# design.net
KiCad netlist of a schematic drawn in Altium Designer
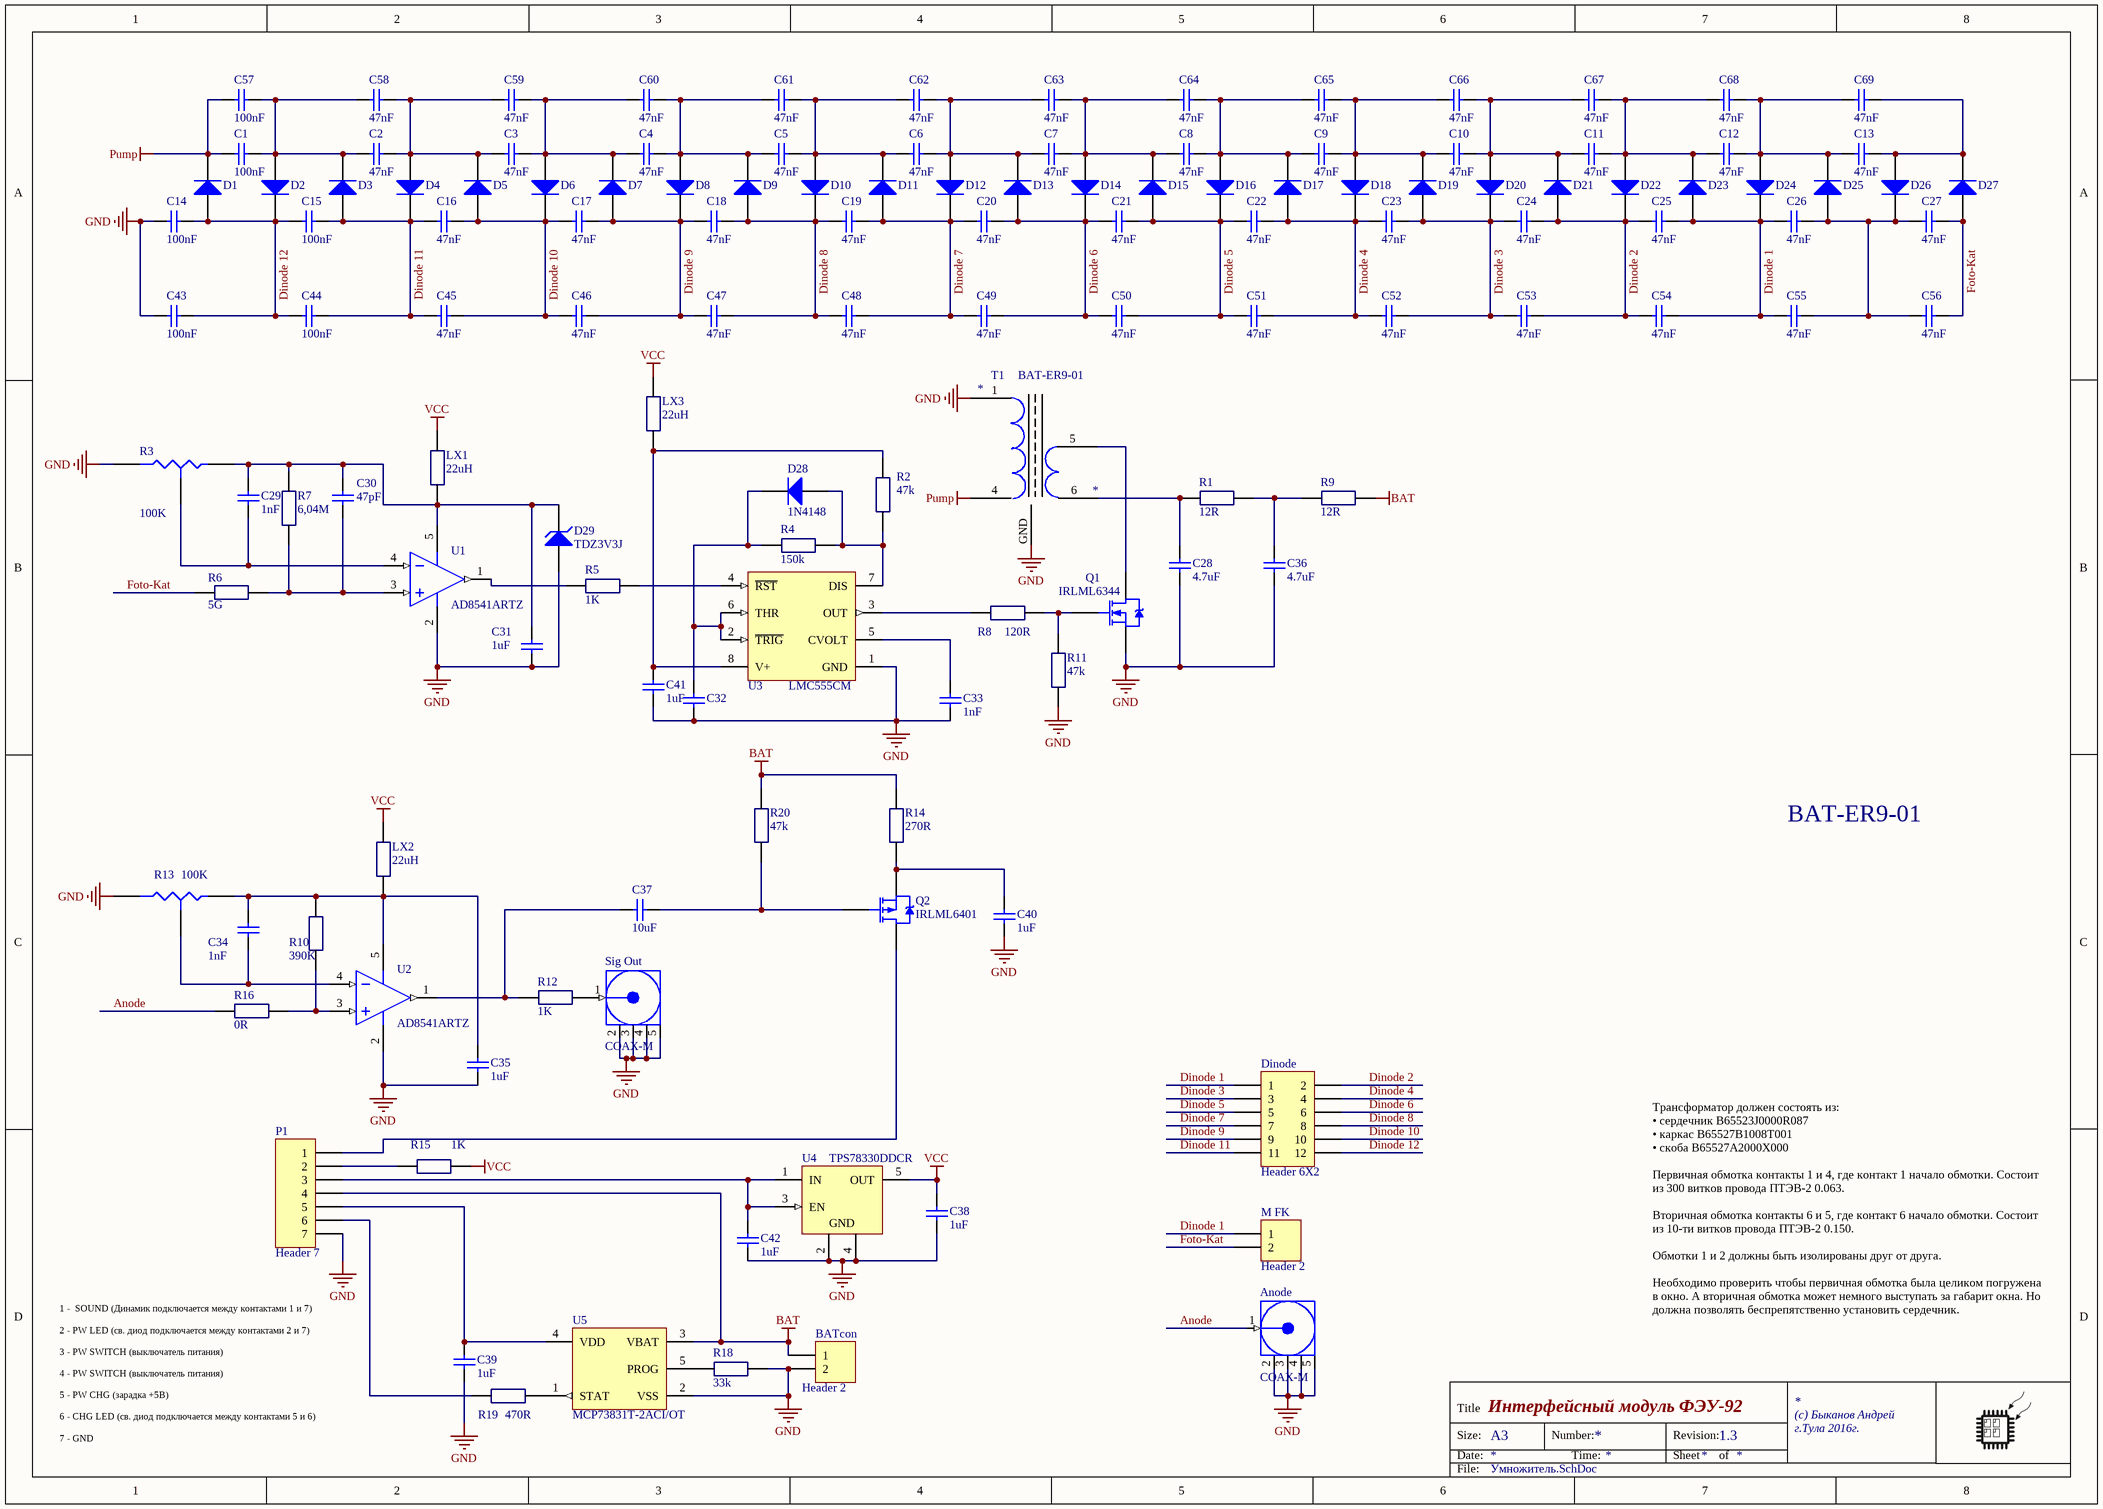
[diagram p0: Умножитель.SchDoc]

(export (version "E")
  (design (tool "Eeschema 10.0.6"))
  (components
    (comp (ref "Anode")
      (value "COAX-M")
      (footprint "MMCX2.54-V5")
      (description "RF Coaxial PCB Connector, MMCX; Thru-Hole, Vertical Mount Plug,  50 Ohm Impedance")
      (libsource (lib "Miscellaneous Connectors") (part "COAX-M"))
    )
    (comp (ref "BATcon")
      (value "Header 2")
      (footprint "LIR2430")
      (description "Header, 2-Pin")
      (libsource (lib "Miscellaneous Connectors") (part "Header 2"))
    )
    (comp (ref "C1")
      (value "100nF")
      (footprint "Miscellaneous Devices:C1206")
      (description "Capacitor (Semiconductor SIM Model)")
      (libsource (lib "Miscellaneous Devices") (part "Cap Semi"))
    )
    (comp (ref "C2")
      (value "47nF")
      (footprint "0805_CAP")
      (description "Capacitor (Semiconductor SIM Model)")
      (libsource (lib "Miscellaneous Devices") (part "Cap Semi"))
    )
    (comp (ref "C3")
      (value "47nF")
      (footprint "0805_CAP")
      (description "Capacitor (Semiconductor SIM Model)")
      (libsource (lib "Miscellaneous Devices") (part "Cap Semi"))
    )
    (comp (ref "C4")
      (value "47nF")
      (footprint "0805_CAP")
      (description "Capacitor (Semiconductor SIM Model)")
      (libsource (lib "Miscellaneous Devices") (part "Cap Semi"))
    )
    (comp (ref "C5")
      (value "47nF")
      (footprint "0805_CAP")
      (description "Capacitor (Semiconductor SIM Model)")
      (libsource (lib "Miscellaneous Devices") (part "Cap Semi"))
    )
    (comp (ref "C6")
      (value "47nF")
      (footprint "0805_CAP")
      (description "Capacitor (Semiconductor SIM Model)")
      (libsource (lib "Miscellaneous Devices") (part "Cap Semi"))
    )
    (comp (ref "C7")
      (value "47nF")
      (footprint "0805_CAP")
      (description "Capacitor (Semiconductor SIM Model)")
      (libsource (lib "Miscellaneous Devices") (part "Cap Semi"))
    )
    (comp (ref "C8")
      (value "47nF")
      (footprint "0805_CAP")
      (description "Capacitor (Semiconductor SIM Model)")
      (libsource (lib "Miscellaneous Devices") (part "Cap Semi"))
    )
    (comp (ref "C9")
      (value "47nF")
      (footprint "0805_CAP")
      (description "Capacitor (Semiconductor SIM Model)")
      (libsource (lib "Miscellaneous Devices") (part "Cap Semi"))
    )
    (comp (ref "C10")
      (value "47nF")
      (footprint "0805_CAP")
      (description "Capacitor (Semiconductor SIM Model)")
      (libsource (lib "Miscellaneous Devices") (part "Cap Semi"))
    )
    (comp (ref "C11")
      (value "47nF")
      (footprint "0805_CAP")
      (description "Capacitor (Semiconductor SIM Model)")
      (libsource (lib "Miscellaneous Devices") (part "Cap Semi"))
    )
    (comp (ref "C12")
      (value "47nF")
      (footprint "0805_CAP")
      (description "Capacitor (Semiconductor SIM Model)")
      (libsource (lib "Miscellaneous Devices") (part "Cap Semi"))
    )
    (comp (ref "C13")
      (value "47nF")
      (footprint "0805_CAP")
      (description "Capacitor (Semiconductor SIM Model)")
      (libsource (lib "Miscellaneous Devices") (part "Cap Semi"))
    )
    (comp (ref "C14")
      (value "100nF")
      (footprint "Miscellaneous Devices:C1206")
      (description "Capacitor (Semiconductor SIM Model)")
      (libsource (lib "Miscellaneous Devices") (part "Cap Semi"))
    )
    (comp (ref "C15")
      (value "100nF")
      (footprint "Miscellaneous Devices:C1206")
      (description "Capacitor (Semiconductor SIM Model)")
      (libsource (lib "Miscellaneous Devices") (part "Cap Semi"))
    )
    (comp (ref "C16")
      (value "47nF")
      (footprint "0805_CAP")
      (description "Capacitor (Semiconductor SIM Model)")
      (libsource (lib "Miscellaneous Devices") (part "Cap Semi"))
    )
    (comp (ref "C17")
      (value "47nF")
      (footprint "0805_CAP")
      (description "Capacitor (Semiconductor SIM Model)")
      (libsource (lib "Miscellaneous Devices") (part "Cap Semi"))
    )
    (comp (ref "C18")
      (value "47nF")
      (footprint "0805_CAP")
      (description "Capacitor (Semiconductor SIM Model)")
      (libsource (lib "Miscellaneous Devices") (part "Cap Semi"))
    )
    (comp (ref "C19")
      (value "47nF")
      (footprint "0805_CAP")
      (description "Capacitor (Semiconductor SIM Model)")
      (libsource (lib "Miscellaneous Devices") (part "Cap Semi"))
    )
    (comp (ref "C20")
      (value "47nF")
      (footprint "0805_CAP")
      (description "Capacitor (Semiconductor SIM Model)")
      (libsource (lib "Miscellaneous Devices") (part "Cap Semi"))
    )
    (comp (ref "C21")
      (value "47nF")
      (footprint "0805_CAP")
      (description "Capacitor (Semiconductor SIM Model)")
      (libsource (lib "Miscellaneous Devices") (part "Cap Semi"))
    )
    (comp (ref "C22")
      (value "47nF")
      (footprint "0805_CAP")
      (description "Capacitor (Semiconductor SIM Model)")
      (libsource (lib "Miscellaneous Devices") (part "Cap Semi"))
    )
    (comp (ref "C23")
      (value "47nF")
      (footprint "0805_CAP")
      (description "Capacitor (Semiconductor SIM Model)")
      (libsource (lib "Miscellaneous Devices") (part "Cap Semi"))
    )
    (comp (ref "C24")
      (value "47nF")
      (footprint "0805_CAP")
      (description "Capacitor (Semiconductor SIM Model)")
      (libsource (lib "Miscellaneous Devices") (part "Cap Semi"))
    )
    (comp (ref "C25")
      (value "47nF")
      (footprint "0805_CAP")
      (description "Capacitor (Semiconductor SIM Model)")
      (libsource (lib "Miscellaneous Devices") (part "Cap Semi"))
    )
    (comp (ref "C26")
      (value "47nF")
      (footprint "0805_CAP")
      (description "Capacitor (Semiconductor SIM Model)")
      (libsource (lib "Miscellaneous Devices") (part "Cap Semi"))
    )
    (comp (ref "C27")
      (value "47nF")
      (footprint "0805_CAP")
      (description "Capacitor (Semiconductor SIM Model)")
      (libsource (lib "Miscellaneous Devices") (part "Cap Semi"))
    )
    (comp (ref "C28")
      (value "4.7uF")
      (footprint "Miscellaneous Devices:C1206")
      (description "Capacitor (Semiconductor SIM Model)")
      (libsource (lib "Miscellaneous Devices") (part "Cap Semi"))
    )
    (comp (ref "C29")
      (value "1nF")
      (footprint "1608[0603]_CAP")
      (description "Capacitor (Semiconductor SIM Model)")
      (libsource (lib "Miscellaneous Devices") (part "Cap Semi"))
    )
    (comp (ref "C30")
      (value "47pF")
      (footprint "1608[0603]_CAP")
      (description "Capacitor (Semiconductor SIM Model)")
      (libsource (lib "Miscellaneous Devices") (part "Cap Semi"))
    )
    (comp (ref "C31")
      (value "1uF")
      (footprint "1608[0603]_CAP")
      (description "Capacitor (Semiconductor SIM Model)")
      (libsource (lib "Miscellaneous Devices") (part "Cap Semi"))
    )
    (comp (ref "C32")
      (value "220pF")
      (footprint "1608[0603]_CAP")
      (description "Capacitor (Semiconductor SIM Model)")
      (libsource (lib "Miscellaneous Devices") (part "Cap Semi"))
    )
    (comp (ref "C33")
      (value "1nF")
      (footprint "1608[0603]_CAP")
      (description "Capacitor (Semiconductor SIM Model)")
      (libsource (lib "Miscellaneous Devices") (part "Cap Semi"))
    )
    (comp (ref "C34")
      (value "1nF")
      (footprint "1608[0603]_CAP")
      (description "Capacitor (Semiconductor SIM Model)")
      (libsource (lib "Miscellaneous Devices") (part "Cap Semi"))
    )
    (comp (ref "C35")
      (value "1uF")
      (footprint "1608[0603]_CAP")
      (description "Capacitor (Semiconductor SIM Model)")
      (libsource (lib "Miscellaneous Devices") (part "Cap Semi"))
    )
    (comp (ref "C36")
      (value "4.7uF")
      (footprint "Miscellaneous Devices:C1206")
      (description "Capacitor (Semiconductor SIM Model)")
      (libsource (lib "Miscellaneous Devices") (part "Cap Semi"))
    )
    (comp (ref "C37")
      (value "10uF")
      (footprint "1608[0603]_CAP")
      (description "Capacitor (Semiconductor SIM Model)")
      (libsource (lib "Miscellaneous Devices") (part "Cap Semi"))
    )
    (comp (ref "C38")
      (value "1uF")
      (footprint "1608[0603]_CAP")
      (description "Capacitor (Semiconductor SIM Model)")
      (libsource (lib "Miscellaneous Devices") (part "Cap Semi"))
    )
    (comp (ref "C39")
      (value "1uF")
      (footprint "1608[0603]_CAP")
      (description "Capacitor (Semiconductor SIM Model)")
      (libsource (lib "Miscellaneous Devices") (part "Cap Semi"))
    )
    (comp (ref "C40")
      (value "1uF")
      (footprint "1608[0603]_CAP")
      (description "Capacitor (Semiconductor SIM Model)")
      (libsource (lib "Miscellaneous Devices") (part "Cap Semi"))
    )
    (comp (ref "C41")
      (value "1uF")
      (footprint "1608[0603]_CAP")
      (description "Capacitor (Semiconductor SIM Model)")
      (libsource (lib "Miscellaneous Devices") (part "Cap Semi"))
    )
    (comp (ref "C42")
      (value "1uF")
      (footprint "1608[0603]_CAP")
      (description "Capacitor (Semiconductor SIM Model)")
      (libsource (lib "Miscellaneous Devices") (part "Cap Semi"))
    )
    (comp (ref "C43")
      (value "100nF")
      (footprint "Miscellaneous Devices:C1206")
      (description "Capacitor (Semiconductor SIM Model)")
      (libsource (lib "Miscellaneous Devices") (part "Cap Semi"))
    )
    (comp (ref "C44")
      (value "100nF")
      (footprint "Miscellaneous Devices:C1206")
      (description "Capacitor (Semiconductor SIM Model)")
      (libsource (lib "Miscellaneous Devices") (part "Cap Semi"))
    )
    (comp (ref "C45")
      (value "47nF")
      (footprint "0805_CAP")
      (description "Capacitor (Semiconductor SIM Model)")
      (libsource (lib "Miscellaneous Devices") (part "Cap Semi"))
    )
    (comp (ref "C46")
      (value "47nF")
      (footprint "0805_CAP")
      (description "Capacitor (Semiconductor SIM Model)")
      (libsource (lib "Miscellaneous Devices") (part "Cap Semi"))
    )
    (comp (ref "C47")
      (value "47nF")
      (footprint "0805_CAP")
      (description "Capacitor (Semiconductor SIM Model)")
      (libsource (lib "Miscellaneous Devices") (part "Cap Semi"))
    )
    (comp (ref "C48")
      (value "47nF")
      (footprint "0805_CAP")
      (description "Capacitor (Semiconductor SIM Model)")
      (libsource (lib "Miscellaneous Devices") (part "Cap Semi"))
    )
    (comp (ref "C49")
      (value "47nF")
      (footprint "0805_CAP")
      (description "Capacitor (Semiconductor SIM Model)")
      (libsource (lib "Miscellaneous Devices") (part "Cap Semi"))
    )
    (comp (ref "C50")
      (value "47nF")
      (footprint "0805_CAP")
      (description "Capacitor (Semiconductor SIM Model)")
      (libsource (lib "Miscellaneous Devices") (part "Cap Semi"))
    )
    (comp (ref "C51")
      (value "47nF")
      (footprint "0805_CAP")
      (description "Capacitor (Semiconductor SIM Model)")
      (libsource (lib "Miscellaneous Devices") (part "Cap Semi"))
    )
    (comp (ref "C52")
      (value "47nF")
      (footprint "0805_CAP")
      (description "Capacitor (Semiconductor SIM Model)")
      (libsource (lib "Miscellaneous Devices") (part "Cap Semi"))
    )
    (comp (ref "C53")
      (value "47nF")
      (footprint "0805_CAP")
      (description "Capacitor (Semiconductor SIM Model)")
      (libsource (lib "Miscellaneous Devices") (part "Cap Semi"))
    )
    (comp (ref "C54")
      (value "47nF")
      (footprint "0805_CAP")
      (description "Capacitor (Semiconductor SIM Model)")
      (libsource (lib "Miscellaneous Devices") (part "Cap Semi"))
    )
    (comp (ref "C55")
      (value "47nF")
      (footprint "0805_CAP")
      (description "Capacitor (Semiconductor SIM Model)")
      (libsource (lib "Miscellaneous Devices") (part "Cap Semi"))
    )
    (comp (ref "C56")
      (value "47nF")
      (footprint "0805_CAP")
      (description "Capacitor (Semiconductor SIM Model)")
      (libsource (lib "Miscellaneous Devices") (part "Cap Semi"))
    )
    (comp (ref "C57")
      (value "100nF")
      (footprint "Miscellaneous Devices:C1206")
      (description "Capacitor (Semiconductor SIM Model)")
      (libsource (lib "Miscellaneous Devices") (part "Cap Semi"))
    )
    (comp (ref "C58")
      (value "47nF")
      (footprint "0805_CAP")
      (description "Capacitor (Semiconductor SIM Model)")
      (libsource (lib "Miscellaneous Devices") (part "Cap Semi"))
    )
    (comp (ref "C59")
      (value "47nF")
      (footprint "0805_CAP")
      (description "Capacitor (Semiconductor SIM Model)")
      (libsource (lib "Miscellaneous Devices") (part "Cap Semi"))
    )
    (comp (ref "C60")
      (value "47nF")
      (footprint "0805_CAP")
      (description "Capacitor (Semiconductor SIM Model)")
      (libsource (lib "Miscellaneous Devices") (part "Cap Semi"))
    )
    (comp (ref "C61")
      (value "47nF")
      (footprint "0805_CAP")
      (description "Capacitor (Semiconductor SIM Model)")
      (libsource (lib "Miscellaneous Devices") (part "Cap Semi"))
    )
    (comp (ref "C62")
      (value "47nF")
      (footprint "0805_CAP")
      (description "Capacitor (Semiconductor SIM Model)")
      (libsource (lib "Miscellaneous Devices") (part "Cap Semi"))
    )
    (comp (ref "C63")
      (value "47nF")
      (footprint "0805_CAP")
      (description "Capacitor (Semiconductor SIM Model)")
      (libsource (lib "Miscellaneous Devices") (part "Cap Semi"))
    )
    (comp (ref "C64")
      (value "47nF")
      (footprint "0805_CAP")
      (description "Capacitor (Semiconductor SIM Model)")
      (libsource (lib "Miscellaneous Devices") (part "Cap Semi"))
    )
    (comp (ref "C65")
      (value "47nF")
      (footprint "0805_CAP")
      (description "Capacitor (Semiconductor SIM Model)")
      (libsource (lib "Miscellaneous Devices") (part "Cap Semi"))
    )
    (comp (ref "C66")
      (value "47nF")
      (footprint "0805_CAP")
      (description "Capacitor (Semiconductor SIM Model)")
      (libsource (lib "Miscellaneous Devices") (part "Cap Semi"))
    )
    (comp (ref "C67")
      (value "47nF")
      (footprint "0805_CAP")
      (description "Capacitor (Semiconductor SIM Model)")
      (libsource (lib "Miscellaneous Devices") (part "Cap Semi"))
    )
    (comp (ref "C68")
      (value "47nF")
      (footprint "0805_CAP")
      (description "Capacitor (Semiconductor SIM Model)")
      (libsource (lib "Miscellaneous Devices") (part "Cap Semi"))
    )
    (comp (ref "C69")
      (value "47nF")
      (footprint "0805_CAP")
      (description "Capacitor (Semiconductor SIM Model)")
      (libsource (lib "Miscellaneous Devices") (part "Cap Semi"))
    )
    (comp (ref "D1")
      (value "~")
      (footprint "DA2JF8100L")
      (description "Default Diode")
      (libsource (lib "Miscellaneous Devices") (part "Diode"))
    )
    (comp (ref "D2")
      (value "~")
      (footprint "DA2JF8100L")
      (description "Default Diode")
      (libsource (lib "Miscellaneous Devices") (part "Diode"))
    )
    (comp (ref "D3")
      (value "~")
      (footprint "DA2JF8100L")
      (description "Default Diode")
      (libsource (lib "Miscellaneous Devices") (part "Diode"))
    )
    (comp (ref "D4")
      (value "~")
      (footprint "DA2JF8100L")
      (description "Default Diode")
      (libsource (lib "Miscellaneous Devices") (part "Diode"))
    )
    (comp (ref "D5")
      (value "~")
      (footprint "DA2JF8100L")
      (description "Default Diode")
      (libsource (lib "Miscellaneous Devices") (part "Diode"))
    )
    (comp (ref "D6")
      (value "~")
      (footprint "DA2JF8100L")
      (description "Default Diode")
      (libsource (lib "Miscellaneous Devices") (part "Diode"))
    )
    (comp (ref "D7")
      (value "~")
      (footprint "DA2JF8100L")
      (description "Default Diode")
      (libsource (lib "Miscellaneous Devices") (part "Diode"))
    )
    (comp (ref "D8")
      (value "~")
      (footprint "DA2JF8100L")
      (description "Default Diode")
      (libsource (lib "Miscellaneous Devices") (part "Diode"))
    )
    (comp (ref "D9")
      (value "~")
      (footprint "DA2JF8100L")
      (description "Default Diode")
      (libsource (lib "Miscellaneous Devices") (part "Diode"))
    )
    (comp (ref "D10")
      (value "~")
      (footprint "DA2JF8100L")
      (description "Default Diode")
      (libsource (lib "Miscellaneous Devices") (part "Diode"))
    )
    (comp (ref "D11")
      (value "~")
      (footprint "DA2JF8100L")
      (description "Default Diode")
      (libsource (lib "Miscellaneous Devices") (part "Diode"))
    )
    (comp (ref "D12")
      (value "~")
      (footprint "DA2JF8100L")
      (description "Default Diode")
      (libsource (lib "Miscellaneous Devices") (part "Diode"))
    )
    (comp (ref "D13")
      (value "~")
      (footprint "DA2JF8100L")
      (description "Default Diode")
      (libsource (lib "Miscellaneous Devices") (part "Diode"))
    )
    (comp (ref "D14")
      (value "~")
      (footprint "DA2JF8100L")
      (description "Default Diode")
      (libsource (lib "Miscellaneous Devices") (part "Diode"))
    )
    (comp (ref "D15")
      (value "~")
      (footprint "DA2JF8100L")
      (description "Default Diode")
      (libsource (lib "Miscellaneous Devices") (part "Diode"))
    )
    (comp (ref "D16")
      (value "~")
      (footprint "DA2JF8100L")
      (description "Default Diode")
      (libsource (lib "Miscellaneous Devices") (part "Diode"))
    )
    (comp (ref "D17")
      (value "~")
      (footprint "DA2JF8100L")
      (description "Default Diode")
      (libsource (lib "Miscellaneous Devices") (part "Diode"))
    )
    (comp (ref "D18")
      (value "~")
      (footprint "DA2JF8100L")
      (description "Default Diode")
      (libsource (lib "Miscellaneous Devices") (part "Diode"))
    )
    (comp (ref "D19")
      (value "~")
      (footprint "DA2JF8100L")
      (description "Default Diode")
      (libsource (lib "Miscellaneous Devices") (part "Diode"))
    )
    (comp (ref "D20")
      (value "~")
      (footprint "DA2JF8100L")
      (description "Default Diode")
      (libsource (lib "Miscellaneous Devices") (part "Diode"))
    )
    (comp (ref "D21")
      (value "~")
      (footprint "DA2JF8100L")
      (description "Default Diode")
      (libsource (lib "Miscellaneous Devices") (part "Diode"))
    )
    (comp (ref "D22")
      (value "~")
      (footprint "DA2JF8100L")
      (description "Default Diode")
      (libsource (lib "Miscellaneous Devices") (part "Diode"))
    )
    (comp (ref "D23")
      (value "~")
      (footprint "DA2JF8100L")
      (description "Default Diode")
      (libsource (lib "Miscellaneous Devices") (part "Diode"))
    )
    (comp (ref "D24")
      (value "~")
      (footprint "DA2JF8100L")
      (description "Default Diode")
      (libsource (lib "Miscellaneous Devices") (part "Diode"))
    )
    (comp (ref "D25")
      (value "~")
      (footprint "DA2JF8100L")
      (description "Default Diode")
      (libsource (lib "Miscellaneous Devices") (part "Diode"))
    )
    (comp (ref "D26")
      (value "~")
      (footprint "DA2JF8100L")
      (description "Default Diode")
      (libsource (lib "Miscellaneous Devices") (part "Diode"))
    )
    (comp (ref "D27")
      (value "~")
      (footprint "DA2JF8100L")
      (description "Default Diode")
      (libsource (lib "Miscellaneous Devices") (part "Diode"))
    )
    (comp (ref "D28")
      (value "1N4148")
      (footprint "GRZZ0002ZB-A")
      (description "Silicon Epitaxial Planar Diode for Various Detector, Modulator, Demodulator")
      (libsource (lib "Renesas Diode") (part "1N4148"))
    )
    (comp (ref "D29")
      (value "TDZ3V3J")
      (footprint "SC-90")
      (description "Zener Diode")
      (libsource (lib "Miscellaneous Devices") (part "D Zener"))
    )
    (comp (ref "Dinode")
      (value "Header 6X2")
      (footprint "HDR2X6")
      (description "Header, 6-Pin, Dual row")
      (libsource (lib "Miscellaneous Connectors") (part "Header 6X2"))
    )
    (comp (ref "LX1")
      (value "22uH")
      (footprint "Resistor")
      (libsource (lib "Микрон-3") (part "Resistor 0805"))
    )
    (comp (ref "LX2")
      (value "22uH")
      (footprint "Resistor")
      (libsource (lib "Микрон-3") (part "Resistor 0805"))
    )
    (comp (ref "LX3")
      (value "22uH")
      (footprint "Resistor")
      (libsource (lib "Микрон-3") (part "Resistor 0805"))
    )
    (comp (ref "M FK")
      (value "Header 2")
      (footprint "HDR1X2")
      (description "Header, 2-Pin")
      (libsource (lib "Miscellaneous Connectors") (part "Header 2"))
    )
    (comp (ref "P1")
      (value "Header 7")
      (footprint "HDR1X7")
      (description "Header, 7-Pin")
      (libsource (lib "Miscellaneous Connectors") (part "Header 7"))
    )
    (comp (ref "Q1")
      (value "IRLML6344")
      (footprint "SOT-23_N")
      (description "HEXFET Power MOSFET")
      (libsource (lib "IR Discrete MOSFET - Power") (part "IRLML2402"))
    )
    (comp (ref "Q2")
      (value "IRLML6401")
      (footprint "Micro3_N")
      (description "HEXFET Power MOSFET")
      (libsource (lib "IR Discrete MOSFET - Power") (part "IRLML6401"))
    )
    (comp (ref "R1")
      (value "12R")
      (footprint "1608[0603]_RES")
      (libsource (lib "Микрон-3") (part "Resistor 0805"))
    )
    (comp (ref "R2")
      (value "47k")
      (footprint "1608[0603]_RES")
      (libsource (lib "Микрон-3") (part "Resistor 0805"))
    )
    (comp (ref "R3")
      (value "100K")
      (footprint "3223W")
      (description "Tapped Resistor")
      (libsource (lib "Miscellaneous Devices") (part "Res Tap"))
    )
    (comp (ref "R4")
      (value "150k")
      (footprint "1608[0603]_RES")
      (libsource (lib "Микрон-3") (part "Resistor 0805"))
    )
    (comp (ref "R5")
      (value "1K")
      (footprint "1608[0603]")
      (libsource (lib "Микрон-3") (part "Resistor 0805"))
    )
    (comp (ref "R6")
      (value "5G")
      (footprint "HVF2512T5007FE")
      (libsource (lib "Микрон-3") (part "Resistor 0805"))
    )
    (comp (ref "R7")
      (value "6,04M")
      (footprint "1608[0603]")
      (libsource (lib "Микрон-3") (part "Resistor 0805"))
    )
    (comp (ref "R8")
      (value "120R")
      (footprint "1608[0603]_RES")
      (libsource (lib "Микрон-3") (part "Resistor 0805"))
    )
    (comp (ref "R9")
      (value "12R")
      (footprint "1608[0603]_RES")
      (libsource (lib "Микрон-3") (part "Resistor 0805"))
    )
    (comp (ref "R10")
      (value "390K")
      (footprint "1608[0603]")
      (libsource (lib "Микрон-3") (part "Resistor 0805"))
    )
    (comp (ref "R11")
      (value "47k")
      (footprint "1608[0603]_RES")
      (libsource (lib "Микрон-3") (part "Resistor 0805"))
    )
    (comp (ref "R12")
      (value "1K")
      (footprint "1608[0603]")
      (libsource (lib "Микрон-3") (part "Resistor 0805"))
    )
    (comp (ref "R13")
      (value "100K")
      (footprint "3223W")
      (description "Tapped Resistor")
      (libsource (lib "Miscellaneous Devices") (part "Res Tap"))
    )
    (comp (ref "R14")
      (value "270R")
      (footprint "1608[0603]_RES")
      (libsource (lib "Микрон-3") (part "Resistor 0805"))
    )
    (comp (ref "R15")
      (value "1K")
      (footprint "1608[0603]_RES")
      (libsource (lib "Микрон-3") (part "Resistor 0805"))
    )
    (comp (ref "R16")
      (value "0R")
      (footprint "1608[0603]")
      (libsource (lib "Микрон-3") (part "Resistor 0805"))
    )
    (comp (ref "R18")
      (value "33k")
      (footprint "1608[0603]_RES")
      (libsource (lib "Микрон-3") (part "Resistor 0805"))
    )
    (comp (ref "R19")
      (value "470R")
      (footprint "1608[0603]_RES")
      (libsource (lib "Микрон-3") (part "Resistor 0805"))
    )
    (comp (ref "R20")
      (value "47k")
      (footprint "1608[0603]_RES")
      (libsource (lib "Микрон-3") (part "Resistor 0805"))
    )
    (comp (ref "Sig Out")
      (value "COAX-M")
      (footprint "MMCX2.54-V5")
      (description "RF Coaxial PCB Connector, MMCX; Thru-Hole, Vertical Mount Plug,  50 Ohm Impedance")
      (libsource (lib "Miscellaneous Connectors") (part "COAX-M"))
    )
    (comp (ref "T1")
      (value "BAT-ER9-01")
      (footprint "Epcos ER9.5/5")
      (libsource (lib "My SCH library") (part "Epcos ER9.5/5"))
    )
    (comp (ref "U1")
      (value "AD8541ARTZ")
      (footprint "ADI-RJ-5_N")
      (fields
        (field (name "GENERIC PART NUMBER") "AD8541")
        (field (name "MANUFACTURER") "Analog Devices")
        (field (name "PARTNUMBER") "AD8541ARTZ-R2")
      )
      (libsource (lib "Analog Devices Operational Amplifiers") (part "AD8541ARTZ-R2"))
    )
    (comp (ref "U2")
      (value "AD8541ARTZ")
      (footprint "ADI-RJ-5_N")
      (fields
        (field (name "GENERIC PART NUMBER") "AD8541")
        (field (name "MANUFACTURER") "Analog Devices")
        (field (name "PARTNUMBER") "AD8541ARTZ-R2")
      )
      (libsource (lib "Analog Devices Operational Amplifiers") (part "AD8541ARTZ-R2"))
    )
    (comp (ref "U3")
      (value "LMC555CM")
      (footprint "M08A_N")
      (description "CMOS Timer, 8-pin Narrow SOIC")
      (fields (field (name "MANUFACTURER") "National Semiconductor"))
      (libsource (lib "NSC Analog") (part "LMC555CM"))
    )
    (comp (ref "U4")
      (value "TPS78330DDCR")
      (footprint "TI-DDC5_N")
      (fields (field (name "MANUFACTURER") "Texas Instruments"))
      (libsource (lib "TI Power Management Linear Regulator Single Channel LDO (0-350mA)") (part "TPS78330DDCR"))
    )
    (comp (ref "U5")
      (value "MCP73831T-2ACI/OT")
      (footprint "SOT-23-OT5_N")
      (libsource (lib "Microchip Power Mgt Battery Management") (part "MCP73831T-2ACI/OT"))
    )
  )
  (nets
    (net (code "1") (name "/Anode") (class "Default")
      (node (ref "Anode") (pin "1") (pinfunction "Signal_1") (pintype "input"))
      (node (ref "R16") (pin "1") (pinfunction "A_1") (pintype "passive"))
    )
    (net (code "2") (name "/Dinode 1") (class "Default")
      (node (ref "C25") (pin "1") (pinfunction "1_1") (pintype "passive"))
      (node (ref "C26") (pin "2") (pinfunction "2_2") (pintype "passive"))
      (node (ref "C54") (pin "1") (pinfunction "1_1") (pintype "passive"))
      (node (ref "C55") (pin "2") (pinfunction "2_2") (pintype "passive"))
      (node (ref "D23") (pin "1") (pinfunction "A_1") (pintype "passive"))
      (node (ref "D24") (pin "2") (pinfunction "K_2") (pintype "passive"))
      (node (ref "Dinode") (pin "1") (pinfunction "1_1") (pintype "passive"))
      (node (ref "M FK") (pin "1") (pinfunction "1_1") (pintype "passive"))
    )
    (net (code "3") (name "/Dinode 2") (class "Default")
      (node (ref "C24") (pin "1") (pinfunction "1_1") (pintype "passive"))
      (node (ref "C25") (pin "2") (pinfunction "2_2") (pintype "passive"))
      (node (ref "C53") (pin "1") (pinfunction "1_1") (pintype "passive"))
      (node (ref "C54") (pin "2") (pinfunction "2_2") (pintype "passive"))
      (node (ref "D21") (pin "1") (pinfunction "A_1") (pintype "passive"))
      (node (ref "D22") (pin "2") (pinfunction "K_2") (pintype "passive"))
      (node (ref "Dinode") (pin "2") (pinfunction "2_2") (pintype "passive"))
    )
    (net (code "4") (name "/Dinode 3") (class "Default")
      (node (ref "C23") (pin "1") (pinfunction "1_1") (pintype "passive"))
      (node (ref "C24") (pin "2") (pinfunction "2_2") (pintype "passive"))
      (node (ref "C52") (pin "1") (pinfunction "1_1") (pintype "passive"))
      (node (ref "C53") (pin "2") (pinfunction "2_2") (pintype "passive"))
      (node (ref "D19") (pin "1") (pinfunction "A_1") (pintype "passive"))
      (node (ref "D20") (pin "2") (pinfunction "K_2") (pintype "passive"))
      (node (ref "Dinode") (pin "3") (pinfunction "3_3") (pintype "passive"))
    )
    (net (code "5") (name "/Dinode 4") (class "Default")
      (node (ref "C22") (pin "1") (pinfunction "1_1") (pintype "passive"))
      (node (ref "C23") (pin "2") (pinfunction "2_2") (pintype "passive"))
      (node (ref "C51") (pin "1") (pinfunction "1_1") (pintype "passive"))
      (node (ref "C52") (pin "2") (pinfunction "2_2") (pintype "passive"))
      (node (ref "D17") (pin "1") (pinfunction "A_1") (pintype "passive"))
      (node (ref "D18") (pin "2") (pinfunction "K_2") (pintype "passive"))
      (node (ref "Dinode") (pin "4") (pinfunction "4_4") (pintype "passive"))
    )
    (net (code "6") (name "/Dinode 5") (class "Default")
      (node (ref "C21") (pin "1") (pinfunction "1_1") (pintype "passive"))
      (node (ref "C22") (pin "2") (pinfunction "2_2") (pintype "passive"))
      (node (ref "C50") (pin "1") (pinfunction "1_1") (pintype "passive"))
      (node (ref "C51") (pin "2") (pinfunction "2_2") (pintype "passive"))
      (node (ref "D15") (pin "1") (pinfunction "A_1") (pintype "passive"))
      (node (ref "D16") (pin "2") (pinfunction "K_2") (pintype "passive"))
      (node (ref "Dinode") (pin "5") (pinfunction "5_5") (pintype "passive"))
    )
    (net (code "7") (name "/Dinode 6") (class "Default")
      (node (ref "C20") (pin "1") (pinfunction "1_1") (pintype "passive"))
      (node (ref "C21") (pin "2") (pinfunction "2_2") (pintype "passive"))
      (node (ref "C49") (pin "1") (pinfunction "1_1") (pintype "passive"))
      (node (ref "C50") (pin "2") (pinfunction "2_2") (pintype "passive"))
      (node (ref "D13") (pin "1") (pinfunction "A_1") (pintype "passive"))
      (node (ref "D14") (pin "2") (pinfunction "K_2") (pintype "passive"))
      (node (ref "Dinode") (pin "6") (pinfunction "6_6") (pintype "passive"))
    )
    (net (code "8") (name "/Dinode 7") (class "Default")
      (node (ref "C19") (pin "1") (pinfunction "1_1") (pintype "passive"))
      (node (ref "C20") (pin "2") (pinfunction "2_2") (pintype "passive"))
      (node (ref "C48") (pin "1") (pinfunction "1_1") (pintype "passive"))
      (node (ref "C49") (pin "2") (pinfunction "2_2") (pintype "passive"))
      (node (ref "D11") (pin "1") (pinfunction "A_1") (pintype "passive"))
      (node (ref "D12") (pin "2") (pinfunction "K_2") (pintype "passive"))
      (node (ref "Dinode") (pin "7") (pinfunction "7_7") (pintype "passive"))
    )
    (net (code "9") (name "/Dinode 8") (class "Default")
      (node (ref "C18") (pin "1") (pinfunction "1_1") (pintype "passive"))
      (node (ref "C19") (pin "2") (pinfunction "2_2") (pintype "passive"))
      (node (ref "C47") (pin "1") (pinfunction "1_1") (pintype "passive"))
      (node (ref "C48") (pin "2") (pinfunction "2_2") (pintype "passive"))
      (node (ref "D10") (pin "2") (pinfunction "K_2") (pintype "passive"))
      (node (ref "D9") (pin "1") (pinfunction "A_1") (pintype "passive"))
      (node (ref "Dinode") (pin "8") (pinfunction "8_8") (pintype "passive"))
    )
    (net (code "10") (name "/Dinode 9") (class "Default")
      (node (ref "C17") (pin "1") (pinfunction "1_1") (pintype "passive"))
      (node (ref "C18") (pin "2") (pinfunction "2_2") (pintype "passive"))
      (node (ref "C46") (pin "1") (pinfunction "1_1") (pintype "passive"))
      (node (ref "C47") (pin "2") (pinfunction "2_2") (pintype "passive"))
      (node (ref "D7") (pin "1") (pinfunction "A_1") (pintype "passive"))
      (node (ref "D8") (pin "2") (pinfunction "K_2") (pintype "passive"))
      (node (ref "Dinode") (pin "9") (pinfunction "9_9") (pintype "passive"))
    )
    (net (code "11") (name "/Dinode 10") (class "Default")
      (node (ref "C16") (pin "1") (pinfunction "1_1") (pintype "passive"))
      (node (ref "C17") (pin "2") (pinfunction "2_2") (pintype "passive"))
      (node (ref "C45") (pin "1") (pinfunction "1_1") (pintype "passive"))
      (node (ref "C46") (pin "2") (pinfunction "2_2") (pintype "passive"))
      (node (ref "D5") (pin "1") (pinfunction "A_1") (pintype "passive"))
      (node (ref "D6") (pin "2") (pinfunction "K_2") (pintype "passive"))
      (node (ref "Dinode") (pin "10") (pinfunction "10_10") (pintype "passive"))
    )
    (net (code "12") (name "/Dinode 11") (class "Default")
      (node (ref "C15") (pin "1") (pinfunction "1_1") (pintype "passive"))
      (node (ref "C16") (pin "2") (pinfunction "2_2") (pintype "passive"))
      (node (ref "C44") (pin "1") (pinfunction "1_1") (pintype "passive"))
      (node (ref "C45") (pin "2") (pinfunction "2_2") (pintype "passive"))
      (node (ref "D3") (pin "1") (pinfunction "A_1") (pintype "passive"))
      (node (ref "D4") (pin "2") (pinfunction "K_2") (pintype "passive"))
      (node (ref "Dinode") (pin "11") (pinfunction "11_11") (pintype "passive"))
    )
    (net (code "13") (name "/Dinode 12") (class "Default")
      (node (ref "C14") (pin "1") (pinfunction "1_1") (pintype "passive"))
      (node (ref "C15") (pin "2") (pinfunction "2_2") (pintype "passive"))
      (node (ref "C43") (pin "1") (pinfunction "1_1") (pintype "passive"))
      (node (ref "C44") (pin "2") (pinfunction "2_2") (pintype "passive"))
      (node (ref "D1") (pin "1") (pinfunction "A_1") (pintype "passive"))
      (node (ref "D2") (pin "2") (pinfunction "K_2") (pintype "passive"))
      (node (ref "Dinode") (pin "12") (pinfunction "12_12") (pintype "passive"))
    )
    (net (code "14") (name "/Foto-Kat") (class "Default")
      (node (ref "C27") (pin "1") (pinfunction "1_1") (pintype "passive"))
      (node (ref "C56") (pin "1") (pinfunction "1_1") (pintype "passive"))
      (node (ref "D27") (pin "1") (pinfunction "A_1") (pintype "passive"))
      (node (ref "M FK") (pin "2") (pinfunction "2_2") (pintype "passive"))
      (node (ref "R6") (pin "1") (pinfunction "A_1") (pintype "passive"))
    )
    (net (code "15") (name "BAT") (class "Default")
      (node (ref "BATcon") (pin "1") (pinfunction "1_1") (pintype "passive"))
      (node (ref "P1") (pin "4") (pinfunction "4_4") (pintype "passive"))
      (node (ref "R14") (pin "2") (pinfunction "2_2") (pintype "passive"))
      (node (ref "R20") (pin "1") (pinfunction "A_1") (pintype "passive"))
      (node (ref "R9") (pin "2") (pinfunction "2_2") (pintype "passive"))
      (node (ref "U5") (pin "3") (pinfunction "VBAT_3") (pintype "power_in"))
    )
    (net (code "16") (name "GND") (class "Default")
      (node (ref "Anode") (pin "2") (pinfunction "GND_2") (pintype "power_in"))
      (node (ref "Anode") (pin "3") (pinfunction "GND_3") (pintype "power_in"))
      (node (ref "Anode") (pin "4") (pinfunction "GND_4") (pintype "power_in"))
      (node (ref "Anode") (pin "5") (pinfunction "GND_5") (pintype "power_in"))
      (node (ref "BATcon") (pin "2") (pinfunction "2_2") (pintype "passive"))
      (node (ref "C14") (pin "2") (pinfunction "2_2") (pintype "passive"))
      (node (ref "C28") (pin "2") (pinfunction "2_2") (pintype "passive"))
      (node (ref "C31") (pin "2") (pinfunction "2_2") (pintype "passive"))
      (node (ref "C32") (pin "1") (pinfunction "1_1") (pintype "passive"))
      (node (ref "C33") (pin "2") (pinfunction "2_2") (pintype "passive"))
      (node (ref "C35") (pin "2") (pinfunction "2_2") (pintype "passive"))
      (node (ref "C36") (pin "2") (pinfunction "2_2") (pintype "passive"))
      (node (ref "C38") (pin "1") (pinfunction "1_1") (pintype "passive"))
      (node (ref "C39") (pin "2") (pinfunction "2_2") (pintype "passive"))
      (node (ref "C40") (pin "2") (pinfunction "2_2") (pintype "passive"))
      (node (ref "C41") (pin "2") (pinfunction "2_2") (pintype "passive"))
      (node (ref "C42") (pin "2") (pinfunction "2_2") (pintype "passive"))
      (node (ref "C43") (pin "2") (pinfunction "2_2") (pintype "passive"))
      (node (ref "D29") (pin "1") (pinfunction "A_1") (pintype "passive"))
      (node (ref "P1") (pin "7") (pinfunction "7_7") (pintype "passive"))
      (node (ref "Q1") (pin "2") (pinfunction "S_2") (pintype "passive"))
      (node (ref "R11") (pin "1") (pinfunction "A_1") (pintype "passive"))
      (node (ref "R13") (pin "2") (pinfunction "B_2") (pintype "passive"))
      (node (ref "R18") (pin "2") (pinfunction "2_2") (pintype "passive"))
      (node (ref "R3") (pin "2") (pinfunction "B_2") (pintype "passive"))
      (node (ref "Sig Out") (pin "2") (pinfunction "GND_2") (pintype "power_in"))
      (node (ref "Sig Out") (pin "3") (pinfunction "GND_3") (pintype "power_in"))
      (node (ref "Sig Out") (pin "4") (pinfunction "GND_4") (pintype "power_in"))
      (node (ref "Sig Out") (pin "5") (pinfunction "GND_5") (pintype "power_in"))
      (node (ref "T1") (pin "1") (pinfunction "1_1") (pintype "passive"))
      (node (ref "T1") (pin "GND") (pinfunction "GND_GND") (pintype "passive"))
      (node (ref "U1") (pin "2") (pinfunction "-V_2") (pintype "power_in"))
      (node (ref "U2") (pin "2") (pinfunction "-V_2") (pintype "power_in"))
      (node (ref "U3") (pin "1") (pinfunction "GND_1") (pintype "power_in"))
      (node (ref "U4") (pin "2") (pinfunction "GND_2") (pintype "power_in"))
      (node (ref "U4") (pin "4") (pinfunction "GND_4") (pintype "power_in"))
      (node (ref "U5") (pin "2") (pinfunction "VSS_2") (pintype "power_in"))
    )
    (net (code "17") (name "Net-(D2-A)") (class "Default")
      (node (ref "C1") (pin "1") (pinfunction "1_1") (pintype "passive"))
      (node (ref "C2") (pin "2") (pinfunction "2_2") (pintype "passive"))
      (node (ref "C57") (pin "1") (pinfunction "1_1") (pintype "passive"))
      (node (ref "C58") (pin "2") (pinfunction "2_2") (pintype "passive"))
      (node (ref "D2") (pin "1") (pinfunction "A_1") (pintype "passive"))
      (node (ref "D3") (pin "2") (pinfunction "K_2") (pintype "passive"))
    )
    (net (code "18") (name "Net-(D4-A)") (class "Default")
      (node (ref "C2") (pin "1") (pinfunction "1_1") (pintype "passive"))
      (node (ref "C3") (pin "2") (pinfunction "2_2") (pintype "passive"))
      (node (ref "C58") (pin "1") (pinfunction "1_1") (pintype "passive"))
      (node (ref "C59") (pin "2") (pinfunction "2_2") (pintype "passive"))
      (node (ref "D4") (pin "1") (pinfunction "A_1") (pintype "passive"))
      (node (ref "D5") (pin "2") (pinfunction "K_2") (pintype "passive"))
    )
    (net (code "19") (name "Net-(D6-A)") (class "Default")
      (node (ref "C3") (pin "1") (pinfunction "1_1") (pintype "passive"))
      (node (ref "C4") (pin "2") (pinfunction "2_2") (pintype "passive"))
      (node (ref "C59") (pin "1") (pinfunction "1_1") (pintype "passive"))
      (node (ref "C60") (pin "2") (pinfunction "2_2") (pintype "passive"))
      (node (ref "D6") (pin "1") (pinfunction "A_1") (pintype "passive"))
      (node (ref "D7") (pin "2") (pinfunction "K_2") (pintype "passive"))
    )
    (net (code "20") (name "Net-(D8-A)") (class "Default")
      (node (ref "C4") (pin "1") (pinfunction "1_1") (pintype "passive"))
      (node (ref "C5") (pin "2") (pinfunction "2_2") (pintype "passive"))
      (node (ref "C60") (pin "1") (pinfunction "1_1") (pintype "passive"))
      (node (ref "C61") (pin "2") (pinfunction "2_2") (pintype "passive"))
      (node (ref "D8") (pin "1") (pinfunction "A_1") (pintype "passive"))
      (node (ref "D9") (pin "2") (pinfunction "K_2") (pintype "passive"))
    )
    (net (code "21") (name "Net-(D10-A)") (class "Default")
      (node (ref "C5") (pin "1") (pinfunction "1_1") (pintype "passive"))
      (node (ref "C6") (pin "2") (pinfunction "2_2") (pintype "passive"))
      (node (ref "C61") (pin "1") (pinfunction "1_1") (pintype "passive"))
      (node (ref "C62") (pin "2") (pinfunction "2_2") (pintype "passive"))
      (node (ref "D10") (pin "1") (pinfunction "A_1") (pintype "passive"))
      (node (ref "D11") (pin "2") (pinfunction "K_2") (pintype "passive"))
    )
    (net (code "22") (name "Net-(D12-A)") (class "Default")
      (node (ref "C6") (pin "1") (pinfunction "1_1") (pintype "passive"))
      (node (ref "C62") (pin "1") (pinfunction "1_1") (pintype "passive"))
      (node (ref "C63") (pin "2") (pinfunction "2_2") (pintype "passive"))
      (node (ref "C7") (pin "2") (pinfunction "2_2") (pintype "passive"))
      (node (ref "D12") (pin "1") (pinfunction "A_1") (pintype "passive"))
      (node (ref "D13") (pin "2") (pinfunction "K_2") (pintype "passive"))
    )
    (net (code "23") (name "Net-(D14-A)") (class "Default")
      (node (ref "C63") (pin "1") (pinfunction "1_1") (pintype "passive"))
      (node (ref "C64") (pin "2") (pinfunction "2_2") (pintype "passive"))
      (node (ref "C7") (pin "1") (pinfunction "1_1") (pintype "passive"))
      (node (ref "C8") (pin "2") (pinfunction "2_2") (pintype "passive"))
      (node (ref "D14") (pin "1") (pinfunction "A_1") (pintype "passive"))
      (node (ref "D15") (pin "2") (pinfunction "K_2") (pintype "passive"))
    )
    (net (code "24") (name "Net-(D16-A)") (class "Default")
      (node (ref "C64") (pin "1") (pinfunction "1_1") (pintype "passive"))
      (node (ref "C65") (pin "2") (pinfunction "2_2") (pintype "passive"))
      (node (ref "C8") (pin "1") (pinfunction "1_1") (pintype "passive"))
      (node (ref "C9") (pin "2") (pinfunction "2_2") (pintype "passive"))
      (node (ref "D16") (pin "1") (pinfunction "A_1") (pintype "passive"))
      (node (ref "D17") (pin "2") (pinfunction "K_2") (pintype "passive"))
    )
    (net (code "25") (name "Net-(D18-A)") (class "Default")
      (node (ref "C10") (pin "2") (pinfunction "2_2") (pintype "passive"))
      (node (ref "C65") (pin "1") (pinfunction "1_1") (pintype "passive"))
      (node (ref "C66") (pin "2") (pinfunction "2_2") (pintype "passive"))
      (node (ref "C9") (pin "1") (pinfunction "1_1") (pintype "passive"))
      (node (ref "D18") (pin "1") (pinfunction "A_1") (pintype "passive"))
      (node (ref "D19") (pin "2") (pinfunction "K_2") (pintype "passive"))
    )
    (net (code "26") (name "Net-(D20-A)") (class "Default")
      (node (ref "C10") (pin "1") (pinfunction "1_1") (pintype "passive"))
      (node (ref "C11") (pin "2") (pinfunction "2_2") (pintype "passive"))
      (node (ref "C66") (pin "1") (pinfunction "1_1") (pintype "passive"))
      (node (ref "C67") (pin "2") (pinfunction "2_2") (pintype "passive"))
      (node (ref "D20") (pin "1") (pinfunction "A_1") (pintype "passive"))
      (node (ref "D21") (pin "2") (pinfunction "K_2") (pintype "passive"))
    )
    (net (code "27") (name "Net-(D22-A)") (class "Default")
      (node (ref "C11") (pin "1") (pinfunction "1_1") (pintype "passive"))
      (node (ref "C12") (pin "2") (pinfunction "2_2") (pintype "passive"))
      (node (ref "C67") (pin "1") (pinfunction "1_1") (pintype "passive"))
      (node (ref "C68") (pin "2") (pinfunction "2_2") (pintype "passive"))
      (node (ref "D22") (pin "1") (pinfunction "A_1") (pintype "passive"))
      (node (ref "D23") (pin "2") (pinfunction "K_2") (pintype "passive"))
    )
    (net (code "28") (name "Net-(D24-A)") (class "Default")
      (node (ref "C12") (pin "1") (pinfunction "1_1") (pintype "passive"))
      (node (ref "C13") (pin "2") (pinfunction "2_2") (pintype "passive"))
      (node (ref "C68") (pin "1") (pinfunction "1_1") (pintype "passive"))
      (node (ref "C69") (pin "2") (pinfunction "2_2") (pintype "passive"))
      (node (ref "D24") (pin "1") (pinfunction "A_1") (pintype "passive"))
      (node (ref "D25") (pin "2") (pinfunction "K_2") (pintype "passive"))
    )
    (net (code "29") (name "Net-(D25-A)") (class "Default")
      (node (ref "C26") (pin "1") (pinfunction "1_1") (pintype "passive"))
      (node (ref "C27") (pin "2") (pinfunction "2_2") (pintype "passive"))
      (node (ref "C55") (pin "1") (pinfunction "1_1") (pintype "passive"))
      (node (ref "C56") (pin "2") (pinfunction "2_2") (pintype "passive"))
      (node (ref "D25") (pin "1") (pinfunction "A_1") (pintype "passive"))
      (node (ref "D26") (pin "2") (pinfunction "K_2") (pintype "passive"))
    )
    (net (code "30") (name "Net-(D26-A)") (class "Default")
      (node (ref "C13") (pin "1") (pinfunction "1_1") (pintype "passive"))
      (node (ref "C69") (pin "1") (pinfunction "1_1") (pintype "passive"))
      (node (ref "D26") (pin "1") (pinfunction "A_1") (pintype "passive"))
      (node (ref "D27") (pin "2") (pinfunction "K_2") (pintype "passive"))
    )
    (net (code "31") (name "Net-(D28-A)") (class "Default")
      (node (ref "D28") (pin "2") (pinfunction "A_2") (pintype "passive"))
      (node (ref "R2") (pin "1") (pinfunction "A_1") (pintype "passive"))
      (node (ref "R4") (pin "2") (pinfunction "2_2") (pintype "passive"))
      (node (ref "U3") (pin "7") (pinfunction "DIS_7") (pintype "open_collector"))
    )
    (net (code "32") (name "Net-(D28-K)") (class "Default")
      (node (ref "C32") (pin "2") (pinfunction "2_2") (pintype "passive"))
      (node (ref "D28") (pin "1") (pinfunction "K_1") (pintype "passive"))
      (node (ref "R4") (pin "1") (pinfunction "A_1") (pintype "passive"))
      (node (ref "U3") (pin "2") (pinfunction "~{TRIG}_2") (pintype "input"))
      (node (ref "U3") (pin "6") (pinfunction "THR_6") (pintype "input"))
    )
    (net (code "33") (name "Net-(D29-K)") (class "Default")
      (node (ref "C29") (pin "1") (pinfunction "1_1") (pintype "passive"))
      (node (ref "C30") (pin "1") (pinfunction "1_1") (pintype "passive"))
      (node (ref "C31") (pin "1") (pinfunction "1_1") (pintype "passive"))
      (node (ref "D29") (pin "2") (pinfunction "K_2") (pintype "passive"))
      (node (ref "LX1") (pin "2") (pinfunction "2_2") (pintype "passive"))
      (node (ref "R3") (pin "1") (pinfunction "A_1") (pintype "passive"))
      (node (ref "R7") (pin "1") (pinfunction "A_1") (pintype "passive"))
      (node (ref "U1") (pin "5") (pinfunction "+V_5") (pintype "power_in"))
    )
    (net (code "34") (name "Net-(P1-Pad2)") (class "Default")
      (node (ref "P1") (pin "2") (pinfunction "2_2") (pintype "passive"))
      (node (ref "R15") (pin "2") (pinfunction "2_2") (pintype "passive"))
    )
    (net (code "35") (name "Net-(P1-Pad6)") (class "Default")
      (node (ref "P1") (pin "6") (pinfunction "6_6") (pintype "passive"))
      (node (ref "R19") (pin "2") (pinfunction "2_2") (pintype "passive"))
    )
    (net (code "36") (name "Net-(Q1-D)") (class "Default")
      (node (ref "Q1") (pin "3") (pinfunction "D_3") (pintype "passive"))
      (node (ref "T1") (pin "5") (pinfunction "5_5") (pintype "passive"))
    )
    (net (code "37") (name "Net-(Q1-G)") (class "Default")
      (node (ref "Q1") (pin "1") (pinfunction "G_1") (pintype "passive"))
      (node (ref "R11") (pin "2") (pinfunction "2_2") (pintype "passive"))
      (node (ref "R8") (pin "1") (pinfunction "A_1") (pintype "passive"))
    )
    (net (code "38") (name "Net-(Q2-D)") (class "Default")
      (node (ref "P1") (pin "1") (pinfunction "1_1") (pintype "passive"))
      (node (ref "Q2") (pin "3") (pinfunction "D_3") (pintype "passive"))
    )
    (net (code "39") (name "Net-(Q2-G)") (class "Default")
      (node (ref "C37") (pin "2") (pinfunction "2_2") (pintype "passive"))
      (node (ref "Q2") (pin "1") (pinfunction "G_1") (pintype "passive"))
      (node (ref "R20") (pin "2") (pinfunction "2_2") (pintype "passive"))
    )
    (net (code "40") (name "Net-(Q2-S)") (class "Default")
      (node (ref "C40") (pin "1") (pinfunction "1_1") (pintype "passive"))
      (node (ref "Q2") (pin "2") (pinfunction "S_2") (pintype "passive"))
      (node (ref "R14") (pin "1") (pinfunction "A_1") (pintype "passive"))
    )
    (net (code "41") (name "Net-(R1-A)") (class "Default")
      (node (ref "C28") (pin "1") (pinfunction "1_1") (pintype "passive"))
      (node (ref "R1") (pin "1") (pinfunction "A_1") (pintype "passive"))
      (node (ref "T1") (pin "6") (pintype "passive"))
    )
    (net (code "42") (name "Net-(R3-TAP)") (class "Default")
      (node (ref "C29") (pin "2") (pinfunction "2_2") (pintype "passive"))
      (node (ref "R3") (pin "3") (pinfunction "TAP_3") (pintype "passive"))
      (node (ref "U1") (pin "4") (pinfunction "-IN_A_4") (pintype "input"))
    )
    (net (code "43") (name "Net-(R5-A)") (class "Default")
      (node (ref "R5") (pin "1") (pinfunction "A_1") (pintype "passive"))
      (node (ref "U1") (pin "1") (pinfunction "OUT_A_1") (pintype "output"))
    )
    (net (code "44") (name "Net-(R9-A)") (class "Default")
      (node (ref "C36") (pin "1") (pinfunction "1_1") (pintype "passive"))
      (node (ref "R1") (pin "2") (pinfunction "2_2") (pintype "passive"))
      (node (ref "R9") (pin "1") (pinfunction "A_1") (pintype "passive"))
    )
    (net (code "45") (name "Net-(R10-A)") (class "Default")
      (node (ref "R10") (pin "1") (pinfunction "A_1") (pintype "passive"))
      (node (ref "R16") (pin "2") (pinfunction "2_2") (pintype "passive"))
      (node (ref "U2") (pin "3") (pinfunction "+IN_A_3") (pintype "input"))
    )
    (net (code "46") (name "Net-(R12-A)") (class "Default")
      (node (ref "R12") (pin "1") (pinfunction "A_1") (pintype "passive"))
      (node (ref "Sig Out") (pin "1") (pinfunction "Signal_1") (pintype "input"))
    )
    (net (code "47") (name "Net-(R13-A)") (class "Default")
      (node (ref "C34") (pin "1") (pinfunction "1_1") (pintype "passive"))
      (node (ref "C35") (pin "1") (pinfunction "1_1") (pintype "passive"))
      (node (ref "LX2") (pin "2") (pinfunction "2_2") (pintype "passive"))
      (node (ref "R10") (pin "2") (pinfunction "2_2") (pintype "passive"))
      (node (ref "R13") (pin "1") (pinfunction "A_1") (pintype "passive"))
      (node (ref "U2") (pin "5") (pinfunction "+V_5") (pintype "power_in"))
    )
    (net (code "48") (name "Net-(R13-TAP)") (class "Default")
      (node (ref "C34") (pin "2") (pinfunction "2_2") (pintype "passive"))
      (node (ref "R13") (pin "3") (pinfunction "TAP_3") (pintype "passive"))
      (node (ref "U2") (pin "4") (pinfunction "-IN_A_4") (pintype "input"))
    )
    (net (code "49") (name "Net-(R18-A)") (class "Default")
      (node (ref "R18") (pin "1") (pinfunction "A_1") (pintype "passive"))
      (node (ref "U5") (pin "5") (pinfunction "PROG_5") (pintype "passive"))
    )
    (net (code "50") (name "Net-(R19-A)") (class "Default")
      (node (ref "R19") (pin "1") (pinfunction "A_1") (pintype "passive"))
      (node (ref "U5") (pin "1") (pinfunction "STAT_1") (pintype "output"))
    )
    (net (code "51") (name "Net-(U1-+IN_A)") (class "Default")
      (node (ref "C30") (pin "2") (pinfunction "2_2") (pintype "passive"))
      (node (ref "R6") (pin "2") (pinfunction "2_2") (pintype "passive"))
      (node (ref "R7") (pin "2") (pinfunction "2_2") (pintype "passive"))
      (node (ref "U1") (pin "3") (pinfunction "+IN_A_3") (pintype "input"))
    )
    (net (code "52") (name "Net-(U2-OUT_A)") (class "Default")
      (node (ref "C37") (pin "1") (pinfunction "1_1") (pintype "passive"))
      (node (ref "R12") (pin "2") (pinfunction "2_2") (pintype "passive"))
      (node (ref "U2") (pin "1") (pinfunction "OUT_A_1") (pintype "output"))
    )
    (net (code "53") (name "Net-(U3-CVOLT)") (class "Default")
      (node (ref "C33") (pin "1") (pinfunction "1_1") (pintype "passive"))
      (node (ref "U3") (pin "5") (pinfunction "CVOLT_5") (pintype "passive"))
    )
    (net (code "54") (name "Net-(U3-OUT)") (class "Default")
      (node (ref "R8") (pin "2") (pinfunction "2_2") (pintype "passive"))
      (node (ref "U3") (pin "3") (pinfunction "OUT_3") (pintype "output"))
    )
    (net (code "55") (name "Net-(U3-V+)") (class "Default")
      (node (ref "C41") (pin "1") (pinfunction "1_1") (pintype "passive"))
      (node (ref "LX3") (pin "2") (pinfunction "2_2") (pintype "passive"))
      (node (ref "R2") (pin "2") (pinfunction "2_2") (pintype "passive"))
      (node (ref "U3") (pin "8") (pinfunction "V+_8") (pintype "power_in"))
    )
    (net (code "56") (name "Net-(U3-~{RST})") (class "Default")
      (node (ref "R5") (pin "2") (pinfunction "2_2") (pintype "passive"))
      (node (ref "U3") (pin "4") (pinfunction "~{RST}_4") (pintype "input"))
    )
    (net (code "57") (name "Net-(U4-EN)") (class "Default")
      (node (ref "C42") (pin "1") (pinfunction "1_1") (pintype "passive"))
      (node (ref "P1") (pin "3") (pinfunction "3_3") (pintype "passive"))
      (node (ref "U4") (pin "1") (pinfunction "IN_1") (pintype "power_in"))
      (node (ref "U4") (pin "3") (pinfunction "EN_3") (pintype "input"))
    )
    (net (code "58") (name "Net-(U5-VDD)") (class "Default")
      (node (ref "C39") (pin "1") (pinfunction "1_1") (pintype "passive"))
      (node (ref "P1") (pin "5") (pinfunction "5_5") (pintype "passive"))
      (node (ref "U5") (pin "4") (pinfunction "VDD_4") (pintype "power_in"))
    )
    (net (code "59") (name "Pump") (class "Default")
      (node (ref "C1") (pin "2") (pinfunction "2_2") (pintype "passive"))
      (node (ref "C57") (pin "2") (pinfunction "2_2") (pintype "passive"))
      (node (ref "D1") (pin "2") (pinfunction "K_2") (pintype "passive"))
      (node (ref "T1") (pin "4") (pinfunction "4_4") (pintype "passive"))
    )
    (net (code "60") (name "VCC") (class "Default")
      (node (ref "C38") (pin "2") (pinfunction "2_2") (pintype "passive"))
      (node (ref "LX1") (pin "1") (pinfunction "A_1") (pintype "passive"))
      (node (ref "LX2") (pin "1") (pinfunction "A_1") (pintype "passive"))
      (node (ref "LX3") (pin "1") (pinfunction "A_1") (pintype "passive"))
      (node (ref "R15") (pin "1") (pinfunction "A_1") (pintype "passive"))
      (node (ref "U4") (pin "5") (pinfunction "OUT_5") (pintype "power_in"))
    )
  )
)
